# 06_LMS7002M_RF2.net
KiCad netlist of a schematic drawn in Altium Designer
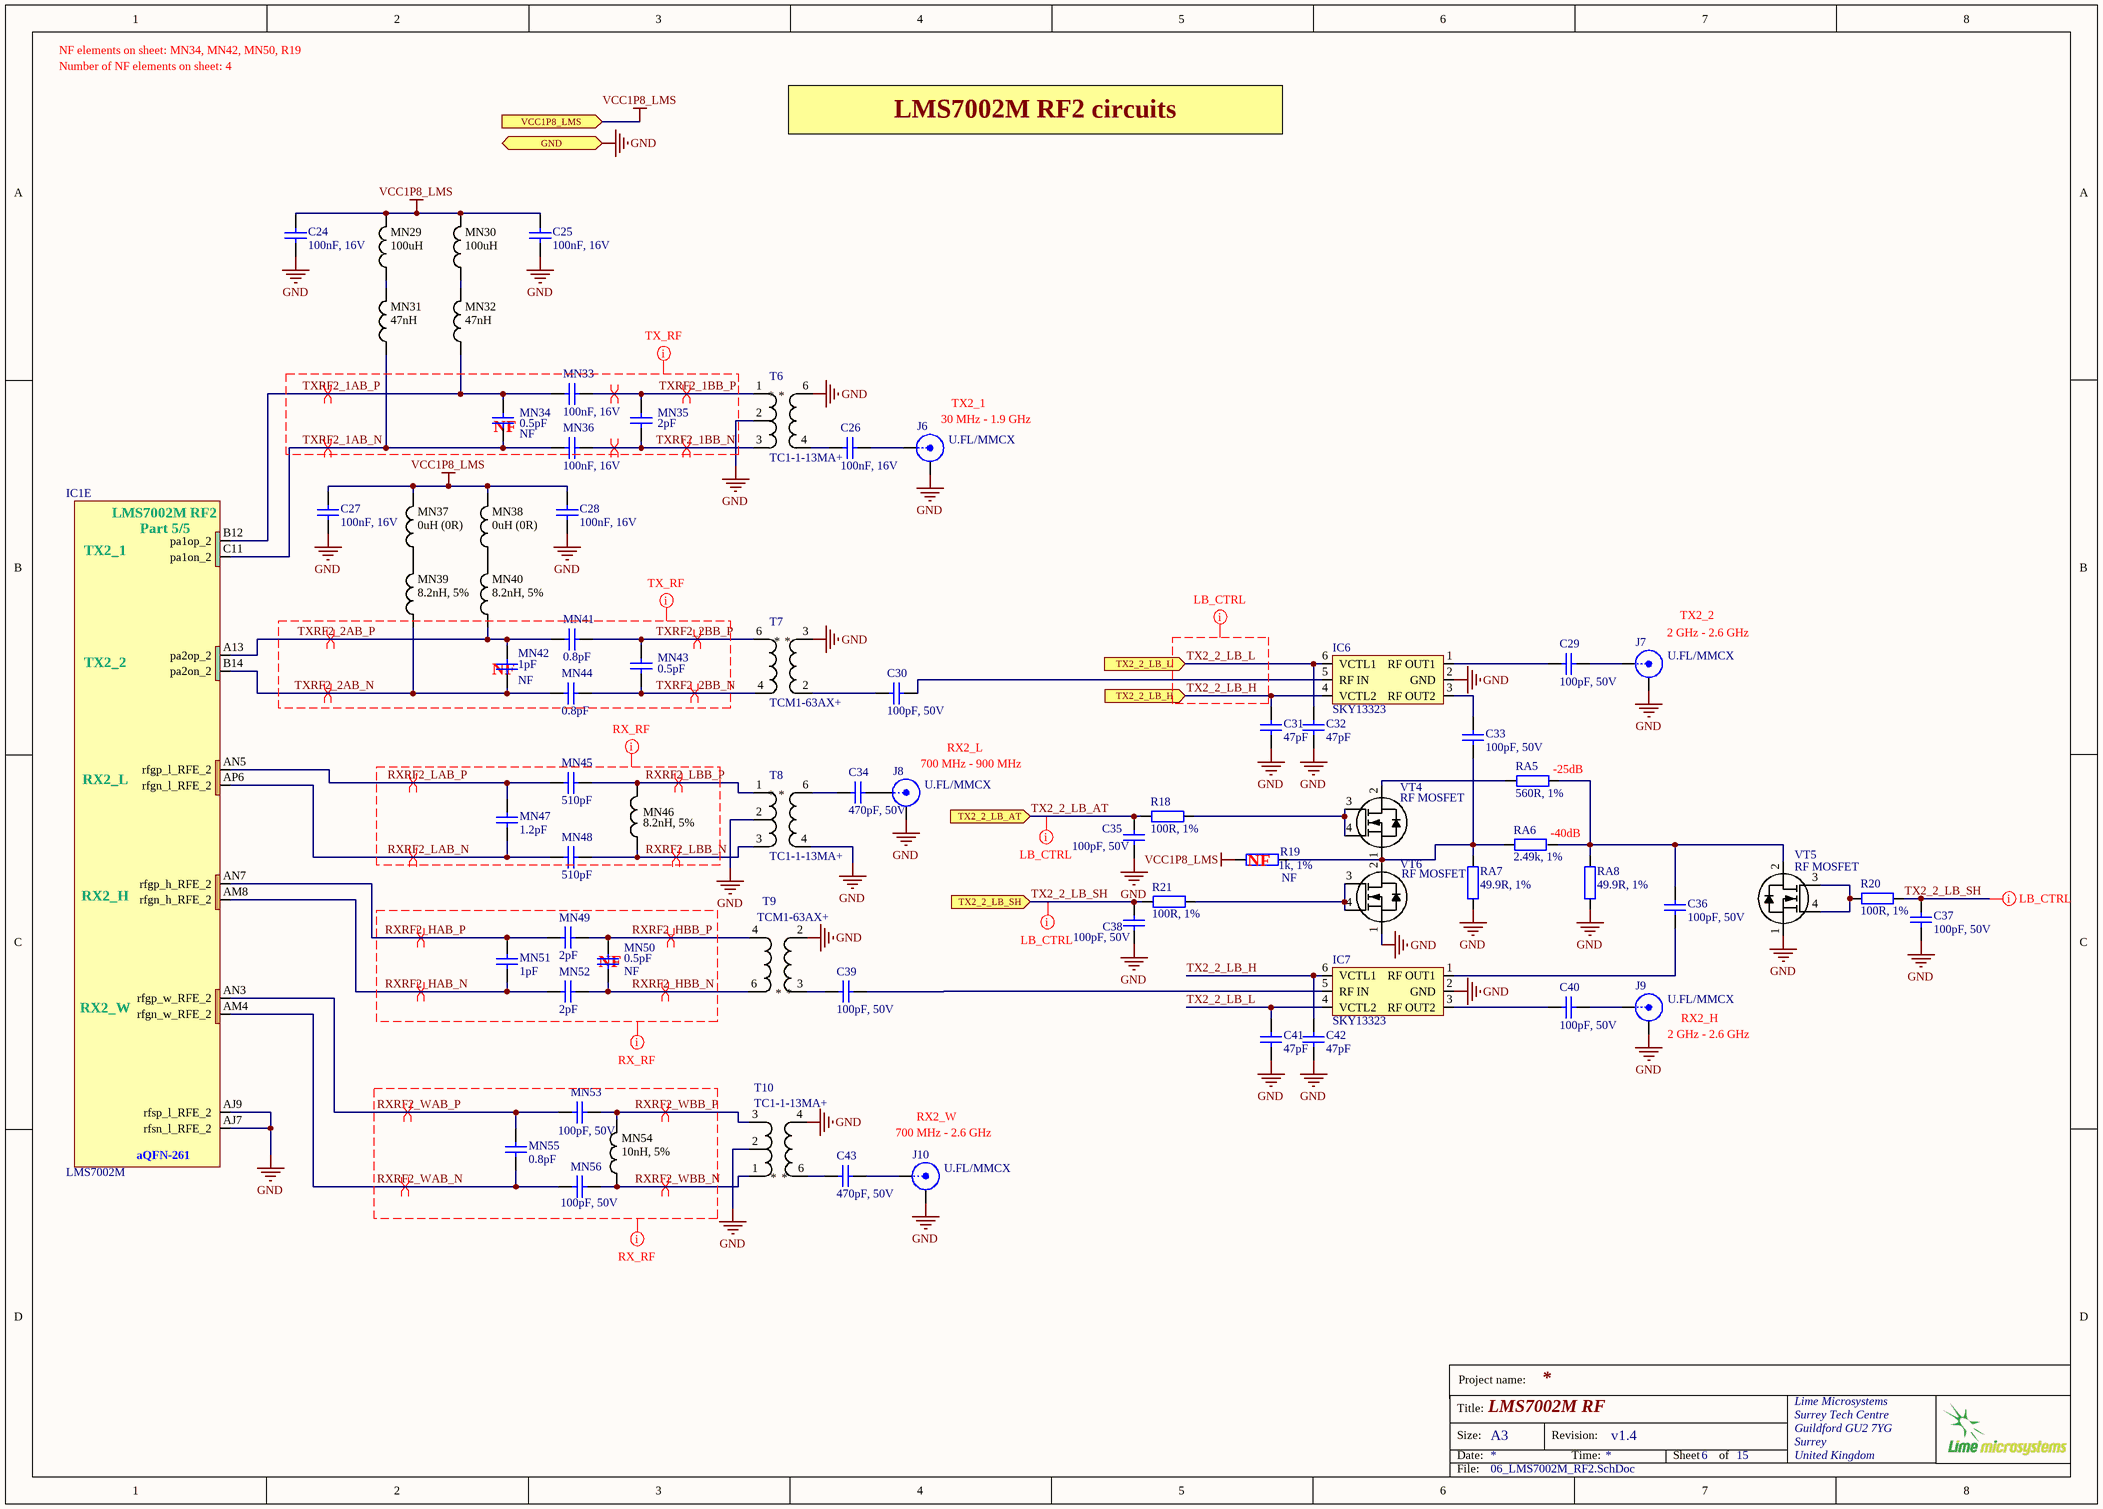
[diagram p0: 06_LMS7002M_RF2.SchDoc]

(export (version "E")
  (design (tool "Eeschema 10.0.6"))
  (components
    (comp (ref "C24")
      (value "100nF, 16V")
      (footprint "CAP0402")
      (fields
        (field (name "MANUFACTURER") "Murata Electronics")
        (field (name "TOLERANCE") "10 %")
        (field (name "MANUFACTURER PART NUMBER") "GRM155R71C104KA88D")
      )
      (libsource (lib "LimeMicroAltiumLib_schLib") (part "Cap_0402"))
    )
    (comp (ref "C25")
      (value "100nF, 16V")
      (footprint "CAP0402")
      (fields
        (field (name "MANUFACTURER") "Murata Electronics")
        (field (name "TOLERANCE") "10 %")
        (field (name "MANUFACTURER PART NUMBER") "GRM155R71C104KA88D")
      )
      (libsource (lib "LimeMicroAltiumLib_schLib") (part "Cap_0402"))
    )
    (comp (ref "C26")
      (value "100nF, 16V")
      (footprint "CAP0402")
      (fields
        (field (name "MANUFACTURER") "Murata Electronics")
        (field (name "TOLERANCE") "10 %")
        (field (name "MANUFACTURER PART NUMBER") "GRM155R71C104KA88D")
      )
      (libsource (lib "LimeMicroAltiumLib_schLib") (part "Cap_0402"))
    )
    (comp (ref "C27")
      (value "100nF, 16V")
      (footprint "CAP0402")
      (fields
        (field (name "MANUFACTURER") "Murata Electronics")
        (field (name "TOLERANCE") "10 %")
        (field (name "MANUFACTURER PART NUMBER") "GRM155R71C104KA88D")
      )
      (libsource (lib "LimeMicroAltiumLib_schLib") (part "Cap_0402"))
    )
    (comp (ref "C28")
      (value "100nF, 16V")
      (footprint "CAP0402")
      (fields
        (field (name "MANUFACTURER") "Murata Electronics")
        (field (name "TOLERANCE") "10 %")
        (field (name "MANUFACTURER PART NUMBER") "GRM155R71C104KA88D")
      )
      (libsource (lib "LimeMicroAltiumLib_schLib") (part "Cap_0402"))
    )
    (comp (ref "C29")
      (value "100pF, 50V")
      (footprint "CAP0402")
      (fields (field (name "TOLERANCE") "±5%") (field (name "MANUFACTURER") "Yageo"))
      (libsource (lib "LimeMicroAltiumLib_schLib") (part "Cap_0402"))
    )
    (comp (ref "C30")
      (value "100pF, 50V")
      (footprint "CAP0402")
      (fields (field (name "TOLERANCE") "±5%") (field (name "MANUFACTURER") "Yageo"))
      (libsource (lib "LimeMicroAltiumLib_schLib") (part "Cap_0402"))
    )
    (comp (ref "C31")
      (value "47pF")
      (footprint "CAP0402")
      (fields (field (name "TOLERANCE") "±1%") (field (name "MANUFACTURER") "TDK Corporation"))
      (libsource (lib "LimeMicroAltiumLib_schLib") (part "Cap_0402"))
    )
    (comp (ref "C32")
      (value "47pF")
      (footprint "CAP0402")
      (fields (field (name "TOLERANCE") "±1%") (field (name "MANUFACTURER") "TDK Corporation"))
      (libsource (lib "LimeMicroAltiumLib_schLib") (part "Cap_0402"))
    )
    (comp (ref "C33")
      (value "100pF, 50V")
      (footprint "CAP0402")
      (fields (field (name "TOLERANCE") "±5%") (field (name "MANUFACTURER") "Yageo"))
      (libsource (lib "LimeMicroAltiumLib_schLib") (part "Cap_0402"))
    )
    (comp (ref "C34")
      (value "470pF, 50V")
      (footprint "CAP0402")
      (fields
        (field (name "MANUFACTURER PART NUMBER") "C1005C0G1H471J050BA")
        (field (name "TOLERANCE") "±5%")
        (field (name "MANUFACTURER") "TDK Corporation")
      )
      (libsource (lib "LimeMicroAltiumLib_schLib") (part "Cap_0402"))
    )
    (comp (ref "C35")
      (value "100pF, 50V")
      (footprint "CAP0402")
      (fields (field (name "TOLERANCE") "±5%") (field (name "MANUFACTURER") "Yageo"))
      (libsource (lib "LimeMicroAltiumLib_schLib") (part "Cap_0402"))
    )
    (comp (ref "C36")
      (value "100pF, 50V")
      (footprint "CAP0402")
      (fields (field (name "TOLERANCE") "±5%") (field (name "MANUFACTURER") "Yageo"))
      (libsource (lib "LimeMicroAltiumLib_schLib") (part "Cap_0402"))
    )
    (comp (ref "C37")
      (value "100pF, 50V")
      (footprint "CAP0402")
      (fields (field (name "TOLERANCE") "±5%") (field (name "MANUFACTURER") "Yageo"))
      (libsource (lib "LimeMicroAltiumLib_schLib") (part "Cap_0402"))
    )
    (comp (ref "C38")
      (value "100pF, 50V")
      (footprint "CAP0402")
      (fields (field (name "TOLERANCE") "±5%") (field (name "MANUFACTURER") "Yageo"))
      (libsource (lib "LimeMicroAltiumLib_schLib") (part "Cap_0402"))
    )
    (comp (ref "C39")
      (value "100pF, 50V")
      (footprint "CAP0402")
      (fields (field (name "TOLERANCE") "±5%") (field (name "MANUFACTURER") "Yageo"))
      (libsource (lib "LimeMicroAltiumLib_schLib") (part "Cap_0402"))
    )
    (comp (ref "C40")
      (value "100pF, 50V")
      (footprint "CAP0402")
      (fields (field (name "TOLERANCE") "±5%") (field (name "MANUFACTURER") "Yageo"))
      (libsource (lib "LimeMicroAltiumLib_schLib") (part "Cap_0402"))
    )
    (comp (ref "C41")
      (value "47pF")
      (footprint "CAP0402")
      (fields (field (name "TOLERANCE") "±1%") (field (name "MANUFACTURER") "TDK Corporation"))
      (libsource (lib "LimeMicroAltiumLib_schLib") (part "Cap_0402"))
    )
    (comp (ref "C42")
      (value "47pF")
      (footprint "CAP0402")
      (fields (field (name "TOLERANCE") "±1%") (field (name "MANUFACTURER") "TDK Corporation"))
      (libsource (lib "LimeMicroAltiumLib_schLib") (part "Cap_0402"))
    )
    (comp (ref "C43")
      (value "470pF, 50V")
      (footprint "CAP0402")
      (fields
        (field (name "MANUFACTURER PART NUMBER") "C1005C0G1H471J050BA")
        (field (name "TOLERANCE") "±5%")
        (field (name "MANUFACTURER") "TDK Corporation")
      )
      (libsource (lib "LimeMicroAltiumLib_schLib") (part "Cap_0402"))
    )
    (comp (ref "IC1")
      (value "LMS7002M")
      (footprint "LMS7002M_v3")
      (fields (field (name "MANUFACTURER") "Lime Microsystems"))
      (libsource (lib "LimeMicroAltiumLib_schLib") (part "LMS7002M"))
    )
    (comp (ref "IC6")
      (value "SKY13323")
      (footprint "SKY13323-378LF")
      (description "SKY13323-378LF: 0.1-3.0 GHz GaAs SPDT Switch")
      (fields (field (name "MANUFACTURER") "Skyworks Solutions Inc."))
      (libsource (lib "LimeMicroAltiumLib_schLib") (part "SKY13323"))
    )
    (comp (ref "IC7")
      (value "SKY13323")
      (footprint "SKY13323-378LF")
      (description "SKY13323-378LF: 0.1-3.0 GHz GaAs SPDT Switch")
      (fields (field (name "MANUFACTURER") "Skyworks Solutions Inc."))
      (libsource (lib "LimeMicroAltiumLib_schLib") (part "SKY13323"))
    )
    (comp (ref "J6")
      (value "U.FL/MMCX")
      (footprint "MMCX_UFL_conn_u")
      (description "CONN UMC RCPT STR 50 OHM SMD")
      (fields (field (name "MANUFACTURER") "Molex, LLC"))
      (libsource (lib "LimeMicroAltiumLib_schLib") (part "RF_IF_connector"))
    )
    (comp (ref "J7")
      (value "U.FL/MMCX")
      (footprint "MMCX_UFL_conn_u")
      (description "CONN UMC RCPT STR 50 OHM SMD")
      (fields (field (name "MANUFACTURER") "Molex, LLC"))
      (libsource (lib "LimeMicroAltiumLib_schLib") (part "RF_IF_connector"))
    )
    (comp (ref "J8")
      (value "U.FL/MMCX")
      (footprint "MMCX_UFL_conn_u")
      (description "CONN UMC RCPT STR 50 OHM SMD")
      (fields (field (name "MANUFACTURER") "Molex, LLC"))
      (libsource (lib "LimeMicroAltiumLib_schLib") (part "RF_IF_connector"))
    )
    (comp (ref "J9")
      (value "U.FL/MMCX")
      (footprint "MMCX_UFL_conn_u")
      (description "CONN UMC RCPT STR 50 OHM SMD")
      (fields (field (name "MANUFACTURER") "Molex, LLC"))
      (libsource (lib "LimeMicroAltiumLib_schLib") (part "RF_IF_connector"))
    )
    (comp (ref "J10")
      (value "U.FL/MMCX")
      (footprint "MMCX_UFL_conn_u")
      (description "CONN UMC RCPT STR 50 OHM SMD")
      (fields (field (name "MANUFACTURER") "Molex, LLC"))
      (libsource (lib "LimeMicroAltiumLib_schLib") (part "RF_IF_connector"))
    )
    (comp (ref "MN29")
      (value "100uH")
      (footprint "RES0805")
      (fields
        (field (name "TOLERANCE") "±10%")
        (field (name "MANUFACTURER") "TDK Corporation")
        (field (name "MANUFACTURER PART NUMBER") "MLF2012C101KT000")
      )
      (libsource (lib "LimeMicroAltiumLib_schLib") (part "Inductor_0603"))
    )
    (comp (ref "MN30")
      (value "100uH")
      (footprint "RES0805")
      (fields
        (field (name "TOLERANCE") "±10%")
        (field (name "MANUFACTURER") "TDK Corporation")
        (field (name "MANUFACTURER PART NUMBER") "MLF2012C101KT000")
      )
      (libsource (lib "LimeMicroAltiumLib_schLib") (part "Inductor_0603"))
    )
    (comp (ref "MN31")
      (value "47nH")
      (footprint "RES0402")
      (fields
        (field (name "MANUFACTURER") "COILCRAFT")
        (field (name "MANUFACTURER PART NUMBER") "0402HP-47NXJLU")
      )
      (libsource (lib "LimeMicroAltiumLib_schLib") (part "Inductor_0603"))
    )
    (comp (ref "MN32")
      (value "47nH")
      (footprint "RES0402")
      (fields
        (field (name "MANUFACTURER") "COILCRAFT")
        (field (name "MANUFACTURER PART NUMBER") "0402HP-47NXJLU")
      )
      (libsource (lib "LimeMicroAltiumLib_schLib") (part "Inductor_0603"))
    )
    (comp (ref "MN33")
      (value "100nF, 16V")
      (footprint "CAP0402")
      (fields
        (field (name "MANUFACTURER") "Murata Electronics")
        (field (name "TOLERANCE") "10 %")
        (field (name "MANUFACTURER PART NUMBER") "GRM155R71C104KA88D")
      )
      (libsource (lib "LimeMicroAltiumLib_schLib") (part "Cap_0402"))
    )
    (comp (ref "MN34")
      (value "0.5pF")
      (footprint "CAP0402")
      (fields
        (field (name "ASSEMBLY INFO") "NF")
        (field (name "TOLERANCE") "±0.25pF")
        (field (name "MANUFACTURER") "Yageo")
      )
      (libsource (lib "LimeMicroAltiumLib_schLib") (part "Cap_0402"))
    )
    (comp (ref "MN35")
      (value "2pF")
      (footprint "CAP0402")
      (fields (field (name "MANUFACTURER PART NUMBER") "04025U2R0BAT2A") (field (name "MANUFACTURER") "AVX"))
      (libsource (lib "LimeMicroAltiumLib_schLib") (part "Cap_0402"))
    )
    (comp (ref "MN36")
      (value "100nF, 16V")
      (footprint "CAP0402")
      (fields
        (field (name "MANUFACTURER") "Murata Electronics")
        (field (name "TOLERANCE") "10 %")
        (field (name "MANUFACTURER PART NUMBER") "GRM155R71C104KA88D")
      )
      (libsource (lib "LimeMicroAltiumLib_schLib") (part "Cap_0402"))
    )
    (comp (ref "MN37")
      (value "0uH (0R)")
      (footprint "RES0805")
      (fields (field (name "MANUFACTURER") "BOURNS"))
      (libsource (lib "LimeMicroAltiumLib_schLib") (part "Inductor_0603"))
    )
    (comp (ref "MN38")
      (value "0uH (0R)")
      (footprint "RES0805")
      (fields (field (name "MANUFACTURER") "BOURNS"))
      (libsource (lib "LimeMicroAltiumLib_schLib") (part "Inductor_0603"))
    )
    (comp (ref "MN39")
      (value "8.2nH, 5%")
      (footprint "RES0402")
      (fields (field (name "MANUFACTURER") "COILCRAFT"))
      (libsource (lib "LimeMicroAltiumLib_schLib") (part "Inductor_0603"))
    )
    (comp (ref "MN40")
      (value "8.2nH, 5%")
      (footprint "RES0402")
      (fields (field (name "MANUFACTURER") "COILCRAFT"))
      (libsource (lib "LimeMicroAltiumLib_schLib") (part "Inductor_0603"))
    )
    (comp (ref "MN41")
      (value "0.8pF")
      (footprint "CAP0402")
      (fields
        (field (name "TOLERANCE") "±0.1pF")
        (field (name "MANUFACTURER") "Murata Electronics North America")
        (field (name "MANUFACTURER PART NUMBER") "GRM1555C1HR80BA01D")
      )
      (libsource (lib "LimeMicroAltiumLib_schLib") (part "Cap_0402"))
    )
    (comp (ref "MN42")
      (value "1pF")
      (footprint "CAP0402")
      (fields
        (field (name "ASSEMBLY INFO") "NF")
        (field (name "MANUFACTURER") "TDK Corporation")
        (field (name "TOLERANCE") "±0.1pF")
      )
      (libsource (lib "LimeMicroAltiumLib_schLib") (part "Cap_0402"))
    )
    (comp (ref "MN43")
      (value "0.5pF")
      (footprint "CAP0402")
      (fields (field (name "TOLERANCE") "±0.25pF") (field (name "MANUFACTURER") "Yageo"))
      (libsource (lib "LimeMicroAltiumLib_schLib") (part "Cap_0402"))
    )
    (comp (ref "MN44")
      (value "0.8pF")
      (footprint "CAP0402")
      (fields
        (field (name "TOLERANCE") "±0.1pF")
        (field (name "MANUFACTURER") "Murata Electronics North America")
        (field (name "MANUFACTURER PART NUMBER") "GRM1555C1HR80BA01D")
      )
      (libsource (lib "LimeMicroAltiumLib_schLib") (part "Cap_0402"))
    )
    (comp (ref "MN45")
      (value "510pF")
      (footprint "CAP0402")
      (fields
        (field (name "TOLERANCE") "±5%")
        (field (name "MANUFACTURER") "Murata Electronics North America")
        (field (name "MANUFACTURER PART NUMBER") "GRM1555C1H511JA01D")
      )
      (libsource (lib "LimeMicroAltiumLib_schLib") (part "Cap_0402"))
    )
    (comp (ref "MN46")
      (value "8.2nH, 5%")
      (footprint "RES0402")
      (fields (field (name "MANUFACTURER") "COILCRAFT"))
      (libsource (lib "LimeMicroAltiumLib_schLib") (part "Inductor_0603"))
    )
    (comp (ref "MN47")
      (value "1.2pF")
      (footprint "CAP0402")
      (fields
        (field (name "MANUFACTURER") "Murata Electronics North America")
        (field (name "MANUFACTURER PART NUMBER") "GRM1555C1H1R2CA01D")
        (field (name "TOLERANCE") "±0.25pF")
      )
      (libsource (lib "LimeMicroAltiumLib_schLib") (part "Cap_0402"))
    )
    (comp (ref "MN48")
      (value "510pF")
      (footprint "CAP0402")
      (fields
        (field (name "TOLERANCE") "±5%")
        (field (name "MANUFACTURER") "Murata Electronics North America")
        (field (name "MANUFACTURER PART NUMBER") "GRM1555C1H511JA01D")
      )
      (libsource (lib "LimeMicroAltiumLib_schLib") (part "Cap_0402"))
    )
    (comp (ref "MN49")
      (value "2pF")
      (footprint "CAP0402")
      (fields (field (name "MANUFACTURER PART NUMBER") "04025U2R0BAT2A") (field (name "MANUFACTURER") "AVX"))
      (libsource (lib "LimeMicroAltiumLib_schLib") (part "Cap_0402"))
    )
    (comp (ref "MN50")
      (value "0.5pF")
      (footprint "CAP0402")
      (fields
        (field (name "ASSEMBLY INFO") "NF")
        (field (name "TOLERANCE") "±0.25pF")
        (field (name "MANUFACTURER") "Yageo")
      )
      (libsource (lib "LimeMicroAltiumLib_schLib") (part "Cap_0402"))
    )
    (comp (ref "MN51")
      (value "1pF")
      (footprint "CAP0402")
      (fields (field (name "MANUFACTURER") "TDK Corporation") (field (name "TOLERANCE") "±0.1pF"))
      (libsource (lib "LimeMicroAltiumLib_schLib") (part "Cap_0402"))
    )
    (comp (ref "MN52")
      (value "2pF")
      (footprint "CAP0402")
      (fields (field (name "MANUFACTURER PART NUMBER") "04025U2R0BAT2A") (field (name "MANUFACTURER") "AVX"))
      (libsource (lib "LimeMicroAltiumLib_schLib") (part "Cap_0402"))
    )
    (comp (ref "MN53")
      (value "100pF, 50V")
      (footprint "CAP0402")
      (fields (field (name "TOLERANCE") "±5%") (field (name "MANUFACTURER") "Yageo"))
      (libsource (lib "LimeMicroAltiumLib_schLib") (part "Cap_0402"))
    )
    (comp (ref "MN54")
      (value "10nH, 5%")
      (footprint "RES0402")
      (fields (field (name "MANUFACTURER") "COILCRAFT"))
      (libsource (lib "LimeMicroAltiumLib_schLib") (part "Inductor_0603"))
    )
    (comp (ref "MN55")
      (value "0.8pF")
      (footprint "CAP0402")
      (fields
        (field (name "TOLERANCE") "±0.1pF")
        (field (name "MANUFACTURER") "Murata Electronics North America")
        (field (name "MANUFACTURER PART NUMBER") "GRM1555C1HR80BA01D")
      )
      (libsource (lib "LimeMicroAltiumLib_schLib") (part "Cap_0402"))
    )
    (comp (ref "MN56")
      (value "100pF, 50V")
      (footprint "CAP0402")
      (fields (field (name "TOLERANCE") "±5%") (field (name "MANUFACTURER") "Yageo"))
      (libsource (lib "LimeMicroAltiumLib_schLib") (part "Cap_0402"))
    )
    (comp (ref "R18")
      (value "100R, 1%")
      (footprint "RES0402")
      (fields (field (name "TOLERANCE") "±1%") (field (name "MANUFACTURER") "Stackpole Electronics Inc."))
      (libsource (lib "LimeFPGAboard_schLib") (part "Res_0402"))
    )
    (comp (ref "R19")
      (value "1k, 1%")
      (footprint "RES0402")
      (fields
        (field (name "ASSEMBLY INFO") "NF")
        (field (name "MANUFACTURER") "Stackpole Electronics Inc")
        (field (name "TOLERANCE") "±1%")
      )
      (libsource (lib "LimeMicroAltiumLib_schLib") (part "Res_0402"))
    )
    (comp (ref "R20")
      (value "100R, 1%")
      (footprint "RES0402")
      (fields (field (name "TOLERANCE") "±1%") (field (name "MANUFACTURER") "Stackpole Electronics Inc."))
      (libsource (lib "LimeFPGAboard_schLib") (part "Res_0402"))
    )
    (comp (ref "R21")
      (value "100R, 1%")
      (footprint "RES0402")
      (fields (field (name "TOLERANCE") "±1%") (field (name "MANUFACTURER") "Stackpole Electronics Inc."))
      (libsource (lib "LimeFPGAboard_schLib") (part "Res_0402"))
    )
    (comp (ref "RA5")
      (value "560R, 1%")
      (footprint "RES0402")
      (fields
        (field (name "MANUFACTURER PART NUMBER") "CRCW0402560RFKED")
        (field (name "TOLERANCE") "±1%")
        (field (name "MANUFACTURER") "Vishay Dale")
      )
      (libsource (lib "LimeMicroAltiumLib_schLib") (part "Res_0402"))
    )
    (comp (ref "RA6")
      (value "2.49k, 1%")
      (footprint "RES0402")
      (fields
        (field (name "TOLERANCE") "±1%")
        (field (name "MANUFACTURER PART NUMBER") "RC0402FR-072K49L")
        (field (name "MANUFACTURER") "Yageo")
      )
      (libsource (lib "LimeMicroAltiumLib_schLib") (part "Res_0402"))
    )
    (comp (ref "RA7")
      (value "49.9R, 1%")
      (footprint "RES0402")
      (fields
        (field (name "TOLERANCE") "±1%")
        (field (name "MANUFACTURER") "Samsung Electro-Mechanics America, Inc.")
        (field (name "MANUFACTURER PART NUMBER") "RC1005F49R9CS")
      )
      (libsource (lib "LimeMicroAltiumLib_schLib") (part "Res_0402"))
    )
    (comp (ref "RA8")
      (value "49.9R, 1%")
      (footprint "RES0402")
      (fields
        (field (name "TOLERANCE") "±1%")
        (field (name "MANUFACTURER") "Samsung Electro-Mechanics America, Inc.")
        (field (name "MANUFACTURER PART NUMBER") "RC1005F49R9CS")
      )
      (libsource (lib "LimeMicroAltiumLib_schLib") (part "Res_0402"))
    )
    (comp (ref "T6")
      (value "TC1-1-13MA+")
      (footprint "TC1-1-13MA+_v2")
      (fields (field (name "MANUFACTURER") "Mini-Circuits"))
      (libsource (lib "") (part "Balun_1"))
    )
    (comp (ref "T7")
      (value "TCM1-63AX+")
      (footprint "TCM1-63AX+_v2")
      (fields (field (name "MANUFACTURER") "Mini-circuits"))
      (libsource (lib "") (part "Balun_v2_1"))
    )
    (comp (ref "T8")
      (value "TC1-1-13MA+")
      (footprint "TC1-1-13MA+_v2")
      (fields (field (name "MANUFACTURER") "Mini-Circuits"))
      (libsource (lib "") (part "Balun_1"))
    )
    (comp (ref "T9")
      (value "TCM1-63AX+")
      (footprint "TCM1-63AX+_v2")
      (fields (field (name "MANUFACTURER") "Mini-circuits"))
      (libsource (lib "LimeMicroAltiumLib_schLib") (part "Balun_v2"))
    )
    (comp (ref "T10")
      (value "TC1-1-13MA+")
      (footprint "TC1-1-13MA+_v2")
      (fields (field (name "MANUFACTURER") "Mini-Circuits"))
      (libsource (lib "LimeMicroAltiumLib_schLib") (part "Balun"))
    )
    (comp (ref "VT4")
      (value "RF MOSFET")
      (footprint "BF1105R_SOT143R4")
      (fields (field (name "MANUFACTURER") "NXP Semiconductors"))
      (libsource (lib "LimeMicroAltiumLib_schLib") (part "BF1105R,215"))
    )
    (comp (ref "VT5")
      (value "RF MOSFET")
      (footprint "BF1105R_SOT143R4")
      (fields (field (name "MANUFACTURER") "NXP Semiconductors"))
      (libsource (lib "LimeMicroAltiumLib_schLib") (part "BF1105R,215"))
    )
    (comp (ref "VT6")
      (value "RF MOSFET")
      (footprint "BF1105R_SOT143R4")
      (fields (field (name "MANUFACTURER") "NXP Semiconductors"))
      (libsource (lib "LimeMicroAltiumLib_schLib") (part "BF1105R,215"))
    )
  )
  (nets
    (net (code "1") (name "/RXRF2_HAB_N") (class "Default")
      (node (ref "IC1") (pin "AM8") (pinfunction "rfgn_h_RFE_2_AM8") (pintype "passive"))
      (node (ref "MN51") (pin "1") (pinfunction "1_1") (pintype "passive"))
      (node (ref "MN52") (pin "2") (pinfunction "2_2") (pintype "passive"))
    )
    (net (code "2") (name "/RXRF2_HAB_P") (class "Default")
      (node (ref "IC1") (pin "AN7") (pinfunction "rfgp_h_RFE_2_AN7") (pintype "passive"))
      (node (ref "MN49") (pin "2") (pinfunction "2_2") (pintype "passive"))
      (node (ref "MN51") (pin "2") (pinfunction "2_2") (pintype "passive"))
    )
    (net (code "3") (name "/RXRF2_HBB_N") (class "Default")
      (node (ref "MN50") (pin "1") (pinfunction "1_1") (pintype "passive"))
      (node (ref "MN52") (pin "1") (pinfunction "1_1") (pintype "passive"))
      (node (ref "T9") (pin "6") (pinfunction "6_6") (pintype "passive"))
    )
    (net (code "4") (name "/RXRF2_HBB_P") (class "Default")
      (node (ref "MN49") (pin "1") (pinfunction "1_1") (pintype "passive"))
      (node (ref "MN50") (pin "2") (pinfunction "2_2") (pintype "passive"))
      (node (ref "T9") (pin "4") (pinfunction "4_4") (pintype "passive"))
    )
    (net (code "5") (name "/RXRF2_LAB_N") (class "Default")
      (node (ref "IC1") (pin "AP6") (pinfunction "rfgn_l_RFE_2_AP6") (pintype "passive"))
      (node (ref "MN47") (pin "1") (pinfunction "1_1") (pintype "passive"))
      (node (ref "MN48") (pin "2") (pinfunction "2_2") (pintype "passive"))
    )
    (net (code "6") (name "/RXRF2_LAB_P") (class "Default")
      (node (ref "IC1") (pin "AN5") (pinfunction "rfgp_l_RFE_2_AN5") (pintype "passive"))
      (node (ref "MN45") (pin "2") (pinfunction "2_2") (pintype "passive"))
      (node (ref "MN47") (pin "2") (pinfunction "2_2") (pintype "passive"))
    )
    (net (code "7") (name "/RXRF2_LBB_N") (class "Default")
      (node (ref "MN46") (pin "1") (pinfunction "1_1") (pintype "passive"))
      (node (ref "MN48") (pin "1") (pinfunction "1_1") (pintype "passive"))
      (node (ref "T8") (pin "3") (pinfunction "3_3") (pintype "passive"))
    )
    (net (code "8") (name "/RXRF2_LBB_P") (class "Default")
      (node (ref "MN45") (pin "1") (pinfunction "1_1") (pintype "passive"))
      (node (ref "MN46") (pin "2") (pinfunction "2_2") (pintype "passive"))
      (node (ref "T8") (pin "1") (pinfunction "1_1") (pintype "passive"))
    )
    (net (code "9") (name "/RXRF2_WAB_N") (class "Default")
      (node (ref "IC1") (pin "AM4") (pinfunction "rfgn_w_RFE_2_AM4") (pintype "passive"))
      (node (ref "MN55") (pin "2") (pinfunction "2_2") (pintype "passive"))
      (node (ref "MN56") (pin "2") (pinfunction "2_2") (pintype "passive"))
    )
    (net (code "10") (name "/RXRF2_WAB_P") (class "Default")
      (node (ref "IC1") (pin "AN3") (pinfunction "rfgp_w_RFE_2_AN3") (pintype "passive"))
      (node (ref "MN53") (pin "2") (pinfunction "2_2") (pintype "passive"))
      (node (ref "MN55") (pin "1") (pinfunction "1_1") (pintype "passive"))
    )
    (net (code "11") (name "/RXRF2_WBB_N") (class "Default")
      (node (ref "MN54") (pin "1") (pinfunction "1_1") (pintype "passive"))
      (node (ref "MN56") (pin "1") (pinfunction "1_1") (pintype "passive"))
      (node (ref "T10") (pin "1") (pinfunction "1_1") (pintype "passive"))
    )
    (net (code "12") (name "/RXRF2_WBB_P") (class "Default")
      (node (ref "MN53") (pin "1") (pinfunction "1_1") (pintype "passive"))
      (node (ref "MN54") (pin "2") (pinfunction "2_2") (pintype "passive"))
      (node (ref "T10") (pin "3") (pinfunction "3_3") (pintype "passive"))
    )
    (net (code "13") (name "/TX2_2_LB_AT") (class "Default")
      (node (ref "C35") (pin "1") (pinfunction "1_1") (pintype "passive"))
      (node (ref "R18") (pin "2") (pinfunction "2_2") (pintype "passive"))
    )
    (net (code "14") (name "/TX2_2_LB_H") (class "Default")
      (node (ref "C31") (pin "2") (pinfunction "2_2") (pintype "passive"))
      (node (ref "C42") (pin "2") (pinfunction "2_2") (pintype "passive"))
      (node (ref "IC6") (pin "4") (pinfunction "VCTL2_4") (pintype "input"))
      (node (ref "IC7") (pin "6") (pinfunction "VCTL1_6") (pintype "input"))
    )
    (net (code "15") (name "/TX2_2_LB_L") (class "Default")
      (node (ref "C32") (pin "2") (pinfunction "2_2") (pintype "passive"))
      (node (ref "C41") (pin "2") (pinfunction "2_2") (pintype "passive"))
      (node (ref "IC6") (pin "6") (pinfunction "VCTL1_6") (pintype "input"))
      (node (ref "IC7") (pin "4") (pinfunction "VCTL2_4") (pintype "input"))
    )
    (net (code "16") (name "/TX2_2_LB_SH") (class "Default")
      (node (ref "C37") (pin "1") (pinfunction "1_1") (pintype "passive"))
      (node (ref "C38") (pin "1") (pinfunction "1_1") (pintype "passive"))
      (node (ref "R20") (pin "1") (pinfunction "1_1") (pintype "passive"))
      (node (ref "R21") (pin "2") (pinfunction "2_2") (pintype "passive"))
    )
    (net (code "17") (name "/TXRF2_1AB_N") (class "Default")
      (node (ref "IC1") (pin "C11") (pinfunction "pa1on_2_C11") (pintype "passive"))
      (node (ref "MN31") (pin "1") (pinfunction "1_1") (pintype "passive"))
      (node (ref "MN34") (pin "1") (pinfunction "1_1") (pintype "passive"))
      (node (ref "MN36") (pin "1") (pinfunction "1_1") (pintype "passive"))
    )
    (net (code "18") (name "/TXRF2_1AB_P") (class "Default")
      (node (ref "IC1") (pin "B12") (pinfunction "pa1op_2_B12") (pintype "passive"))
      (node (ref "MN32") (pin "1") (pinfunction "1_1") (pintype "passive"))
      (node (ref "MN33") (pin "2") (pinfunction "2_2") (pintype "passive"))
      (node (ref "MN34") (pin "2") (pinfunction "2_2") (pintype "passive"))
    )
    (net (code "19") (name "/TXRF2_1BB_N") (class "Default")
      (node (ref "MN35") (pin "1") (pinfunction "1_1") (pintype "passive"))
      (node (ref "MN36") (pin "2") (pinfunction "2_2") (pintype "passive"))
      (node (ref "T6") (pin "3") (pinfunction "3_3") (pintype "passive"))
    )
    (net (code "20") (name "/TXRF2_1BB_P") (class "Default")
      (node (ref "MN33") (pin "1") (pinfunction "1_1") (pintype "passive"))
      (node (ref "MN35") (pin "2") (pinfunction "2_2") (pintype "passive"))
      (node (ref "T6") (pin "1") (pinfunction "1_1") (pintype "passive"))
    )
    (net (code "21") (name "/TXRF2_2AB_N") (class "Default")
      (node (ref "IC1") (pin "B14") (pinfunction "pa2on_2_B14") (pintype "passive"))
      (node (ref "MN39") (pin "1") (pinfunction "1_1") (pintype "passive"))
      (node (ref "MN42") (pin "2") (pinfunction "2_2") (pintype "passive"))
      (node (ref "MN44") (pin "2") (pinfunction "2_2") (pintype "passive"))
    )
    (net (code "22") (name "/TXRF2_2AB_P") (class "Default")
      (node (ref "IC1") (pin "A13") (pinfunction "pa2op_2_A13") (pintype "passive"))
      (node (ref "MN40") (pin "1") (pinfunction "1_1") (pintype "passive"))
      (node (ref "MN41") (pin "2") (pinfunction "2_2") (pintype "passive"))
      (node (ref "MN42") (pin "1") (pinfunction "1_1") (pintype "passive"))
    )
    (net (code "23") (name "/TXRF2_2BB_N") (class "Default")
      (node (ref "MN43") (pin "1") (pinfunction "1_1") (pintype "passive"))
      (node (ref "MN44") (pin "1") (pinfunction "1_1") (pintype "passive"))
      (node (ref "T7") (pin "4") (pinfunction "4_4") (pintype "passive"))
    )
    (net (code "24") (name "/TXRF2_2BB_P") (class "Default")
      (node (ref "MN41") (pin "1") (pinfunction "1_1") (pintype "passive"))
      (node (ref "MN43") (pin "2") (pinfunction "2_2") (pintype "passive"))
      (node (ref "T7") (pin "6") (pinfunction "6_6") (pintype "passive"))
    )
    (net (code "25") (name "GND") (class "Default")
      (node (ref "C24") (pin "1") (pinfunction "1_1") (pintype "passive"))
      (node (ref "C25") (pin "1") (pinfunction "1_1") (pintype "passive"))
      (node (ref "C27") (pin "1") (pinfunction "1_1") (pintype "passive"))
      (node (ref "C28") (pin "1") (pinfunction "1_1") (pintype "passive"))
      (node (ref "C31") (pin "1") (pinfunction "1_1") (pintype "passive"))
      (node (ref "C32") (pin "1") (pinfunction "1_1") (pintype "passive"))
      (node (ref "C35") (pin "2") (pinfunction "2_2") (pintype "passive"))
      (node (ref "C37") (pin "2") (pinfunction "2_2") (pintype "passive"))
      (node (ref "C38") (pin "2") (pinfunction "2_2") (pintype "passive"))
      (node (ref "C41") (pin "1") (pinfunction "1_1") (pintype "passive"))
      (node (ref "C42") (pin "1") (pinfunction "1_1") (pintype "passive"))
      (node (ref "IC1") (pin "AJ7") (pinfunction "rfsn_l_RFE_2_AJ7") (pintype "passive"))
      (node (ref "IC1") (pin "AJ9") (pinfunction "rfsp_l_RFE_2_AJ9") (pintype "passive"))
      (node (ref "IC6") (pin "2") (pinfunction "GND_2") (pintype "passive"))
      (node (ref "IC7") (pin "2") (pinfunction "GND_2") (pintype "passive"))
      (node (ref "J10") (pin "2") (pinfunction "Y_2") (pintype "passive"))
      (node (ref "J6") (pin "2") (pinfunction "Y_2") (pintype "passive"))
      (node (ref "J7") (pin "2") (pinfunction "Y_2") (pintype "passive"))
      (node (ref "J8") (pin "2") (pinfunction "Y_2") (pintype "passive"))
      (node (ref "J9") (pin "2") (pinfunction "Y_2") (pintype "passive"))
      (node (ref "RA7") (pin "1") (pinfunction "1_1") (pintype "passive"))
      (node (ref "RA8") (pin "1") (pinfunction "1_1") (pintype "passive"))
      (node (ref "T10") (pin "2") (pinfunction "2_2") (pintype "passive"))
      (node (ref "T10") (pin "4") (pinfunction "4_4") (pintype "passive"))
      (node (ref "T6") (pin "2") (pinfunction "2_2") (pintype "passive"))
      (node (ref "T6") (pin "6") (pinfunction "6_6") (pintype "passive"))
      (node (ref "T7") (pin "3") (pinfunction "3_3") (pintype "passive"))
      (node (ref "T8") (pin "2") (pinfunction "2_2") (pintype "passive"))
      (node (ref "T8") (pin "4") (pinfunction "4_4") (pintype "passive"))
      (node (ref "T9") (pin "2") (pinfunction "2_2") (pintype "passive"))
      (node (ref "VT5") (pin "1") (pinfunction "S_1") (pintype "passive"))
      (node (ref "VT6") (pin "1") (pinfunction "S_1") (pintype "passive"))
    )
    (net (code "26") (name "Net-(C26-Pad2)") (class "Default")
      (node (ref "C26") (pin "2") (pinfunction "2_2") (pintype "passive"))
      (node (ref "T6") (pin "4") (pinfunction "4_4") (pintype "passive"))
    )
    (net (code "27") (name "Net-(C30-Pad2)") (class "Default")
      (node (ref "C30") (pin "2") (pinfunction "2_2") (pintype "passive"))
      (node (ref "T7") (pin "2") (pinfunction "2_2") (pintype "passive"))
    )
    (net (code "28") (name "Net-(C34-Pad2)") (class "Default")
      (node (ref "C34") (pin "2") (pinfunction "2_2") (pintype "passive"))
      (node (ref "T8") (pin "6") (pinfunction "6_6") (pintype "passive"))
    )
    (net (code "29") (name "Net-(C39-Pad2)") (class "Default")
      (node (ref "C39") (pin "2") (pinfunction "2_2") (pintype "passive"))
      (node (ref "T9") (pin "3") (pinfunction "3_3") (pintype "passive"))
    )
    (net (code "30") (name "Net-(C43-Pad2)") (class "Default")
      (node (ref "C43") (pin "2") (pinfunction "2_2") (pintype "passive"))
      (node (ref "T10") (pin "6") (pinfunction "6_6") (pintype "passive"))
    )
    (net (code "31") (name "Net-(IC6-RF_IN)") (class "Default")
      (node (ref "C30") (pin "1") (pinfunction "1_1") (pintype "passive"))
      (node (ref "IC6") (pin "5") (pinfunction "RF_IN_5") (pintype "input"))
    )
    (net (code "32") (name "Net-(IC6-RF_OUT1)") (class "Default")
      (node (ref "C29") (pin "2") (pinfunction "2_2") (pintype "passive"))
      (node (ref "IC6") (pin "1") (pinfunction "RF_OUT1_1") (pintype "output"))
    )
    (net (code "33") (name "Net-(IC6-RF_OUT2)") (class "Default")
      (node (ref "C33") (pin "1") (pinfunction "1_1") (pintype "passive"))
      (node (ref "IC6") (pin "3") (pinfunction "RF_OUT2_3") (pintype "output"))
    )
    (net (code "34") (name "Net-(IC7-RF_IN)") (class "Default")
      (node (ref "C39") (pin "1") (pinfunction "1_1") (pintype "passive"))
      (node (ref "IC7") (pin "5") (pinfunction "RF_IN_5") (pintype "input"))
    )
    (net (code "35") (name "Net-(IC7-RF_OUT1)") (class "Default")
      (node (ref "C36") (pin "2") (pinfunction "2_2") (pintype "passive"))
      (node (ref "IC7") (pin "1") (pinfunction "RF_OUT1_1") (pintype "output"))
    )
    (net (code "36") (name "Net-(IC7-RF_OUT2)") (class "Default")
      (node (ref "C40") (pin "2") (pinfunction "2_2") (pintype "passive"))
      (node (ref "IC7") (pin "3") (pinfunction "RF_OUT2_3") (pintype "output"))
    )
    (net (code "37") (name "Net-(J6-X)") (class "Default")
      (node (ref "C26") (pin "1") (pinfunction "1_1") (pintype "passive"))
      (node (ref "J6") (pin "1") (pinfunction "X_1") (pintype "passive"))
    )
    (net (code "38") (name "Net-(J7-X)") (class "Default")
      (node (ref "C29") (pin "1") (pinfunction "1_1") (pintype "passive"))
      (node (ref "J7") (pin "1") (pinfunction "X_1") (pintype "passive"))
    )
    (net (code "39") (name "Net-(J8-X)") (class "Default")
      (node (ref "C34") (pin "1") (pinfunction "1_1") (pintype "passive"))
      (node (ref "J8") (pin "1") (pinfunction "X_1") (pintype "passive"))
    )
    (net (code "40") (name "Net-(J9-X)") (class "Default")
      (node (ref "C40") (pin "1") (pinfunction "1_1") (pintype "passive"))
      (node (ref "J9") (pin "1") (pinfunction "X_1") (pintype "passive"))
    )
    (net (code "41") (name "Net-(J10-X)") (class "Default")
      (node (ref "C43") (pin "1") (pinfunction "1_1") (pintype "passive"))
      (node (ref "J10") (pin "1") (pinfunction "X_1") (pintype "passive"))
    )
    (net (code "42") (name "Net-(MN29-Pad1)") (class "Default")
      (node (ref "MN29") (pin "1") (pinfunction "1_1") (pintype "passive"))
      (node (ref "MN31") (pin "2") (pinfunction "2_2") (pintype "passive"))
    )
    (net (code "43") (name "Net-(MN30-Pad1)") (class "Default")
      (node (ref "MN30") (pin "1") (pinfunction "1_1") (pintype "passive"))
      (node (ref "MN32") (pin "2") (pinfunction "2_2") (pintype "passive"))
    )
    (net (code "44") (name "Net-(MN37-Pad1)") (class "Default")
      (node (ref "MN37") (pin "1") (pinfunction "1_1") (pintype "passive"))
      (node (ref "MN39") (pin "2") (pinfunction "2_2") (pintype "passive"))
    )
    (net (code "45") (name "Net-(MN38-Pad1)") (class "Default")
      (node (ref "MN38") (pin "1") (pinfunction "1_1") (pintype "passive"))
      (node (ref "MN40") (pin "2") (pinfunction "2_2") (pintype "passive"))
    )
    (net (code "46") (name "Net-(VT4-D)") (class "Default")
      (node (ref "RA5") (pin "2") (pinfunction "2_2") (pintype "passive"))
      (node (ref "VT4") (pin "2") (pinfunction "D_2") (pintype "passive"))
    )
    (net (code "47") (name "Net-(VT4-G1)") (class "Default")
      (node (ref "R18") (pin "1") (pinfunction "1_1") (pintype "passive"))
      (node (ref "VT4") (pin "3") (pinfunction "G2_3") (pintype "passive"))
      (node (ref "VT4") (pin "4") (pinfunction "G1_4") (pintype "passive"))
    )
    (net (code "48") (name "Net-(VT4-S)") (class "Default")
      (node (ref "C33") (pin "2") (pinfunction "2_2") (pintype "passive"))
      (node (ref "R19") (pin "1") (pinfunction "1_1") (pintype "passive"))
      (node (ref "RA6") (pin "1") (pinfunction "1_1") (pintype "passive"))
      (node (ref "RA7") (pin "2") (pinfunction "2_2") (pintype "passive"))
      (node (ref "VT4") (pin "1") (pinfunction "S_1") (pintype "passive"))
      (node (ref "VT6") (pin "2") (pinfunction "D_2") (pintype "passive"))
    )
    (net (code "49") (name "Net-(VT5-D)") (class "Default")
      (node (ref "C36") (pin "1") (pinfunction "1_1") (pintype "passive"))
      (node (ref "RA5") (pin "1") (pinfunction "1_1") (pintype "passive"))
      (node (ref "RA6") (pin "2") (pinfunction "2_2") (pintype "passive"))
      (node (ref "RA8") (pin "2") (pinfunction "2_2") (pintype "passive"))
      (node (ref "VT5") (pin "2") (pinfunction "D_2") (pintype "passive"))
    )
    (net (code "50") (name "Net-(VT5-G1)") (class "Default")
      (node (ref "R20") (pin "2") (pinfunction "2_2") (pintype "passive"))
      (node (ref "VT5") (pin "3") (pinfunction "G2_3") (pintype "passive"))
      (node (ref "VT5") (pin "4") (pinfunction "G1_4") (pintype "passive"))
    )
    (net (code "51") (name "Net-(VT6-G1)") (class "Default")
      (node (ref "R21") (pin "1") (pinfunction "1_1") (pintype "passive"))
      (node (ref "VT6") (pin "3") (pinfunction "G2_3") (pintype "passive"))
      (node (ref "VT6") (pin "4") (pinfunction "G1_4") (pintype "passive"))
    )
    (net (code "52") (name "VCC1P8_LMS") (class "Default")
      (node (ref "C24") (pin "2") (pinfunction "2_2") (pintype "passive"))
      (node (ref "C25") (pin "2") (pinfunction "2_2") (pintype "passive"))
      (node (ref "C27") (pin "2") (pinfunction "2_2") (pintype "passive"))
      (node (ref "C28") (pin "2") (pinfunction "2_2") (pintype "passive"))
      (node (ref "MN29") (pin "2") (pinfunction "2_2") (pintype "passive"))
      (node (ref "MN30") (pin "2") (pinfunction "2_2") (pintype "passive"))
      (node (ref "MN37") (pin "2") (pinfunction "2_2") (pintype "passive"))
      (node (ref "MN38") (pin "2") (pinfunction "2_2") (pintype "passive"))
      (node (ref "R19") (pin "2") (pinfunction "2_2") (pintype "passive"))
    )
  )
)
